# Nixie_Clock.net
KiCad netlist of a schematic drawn in EAGLE
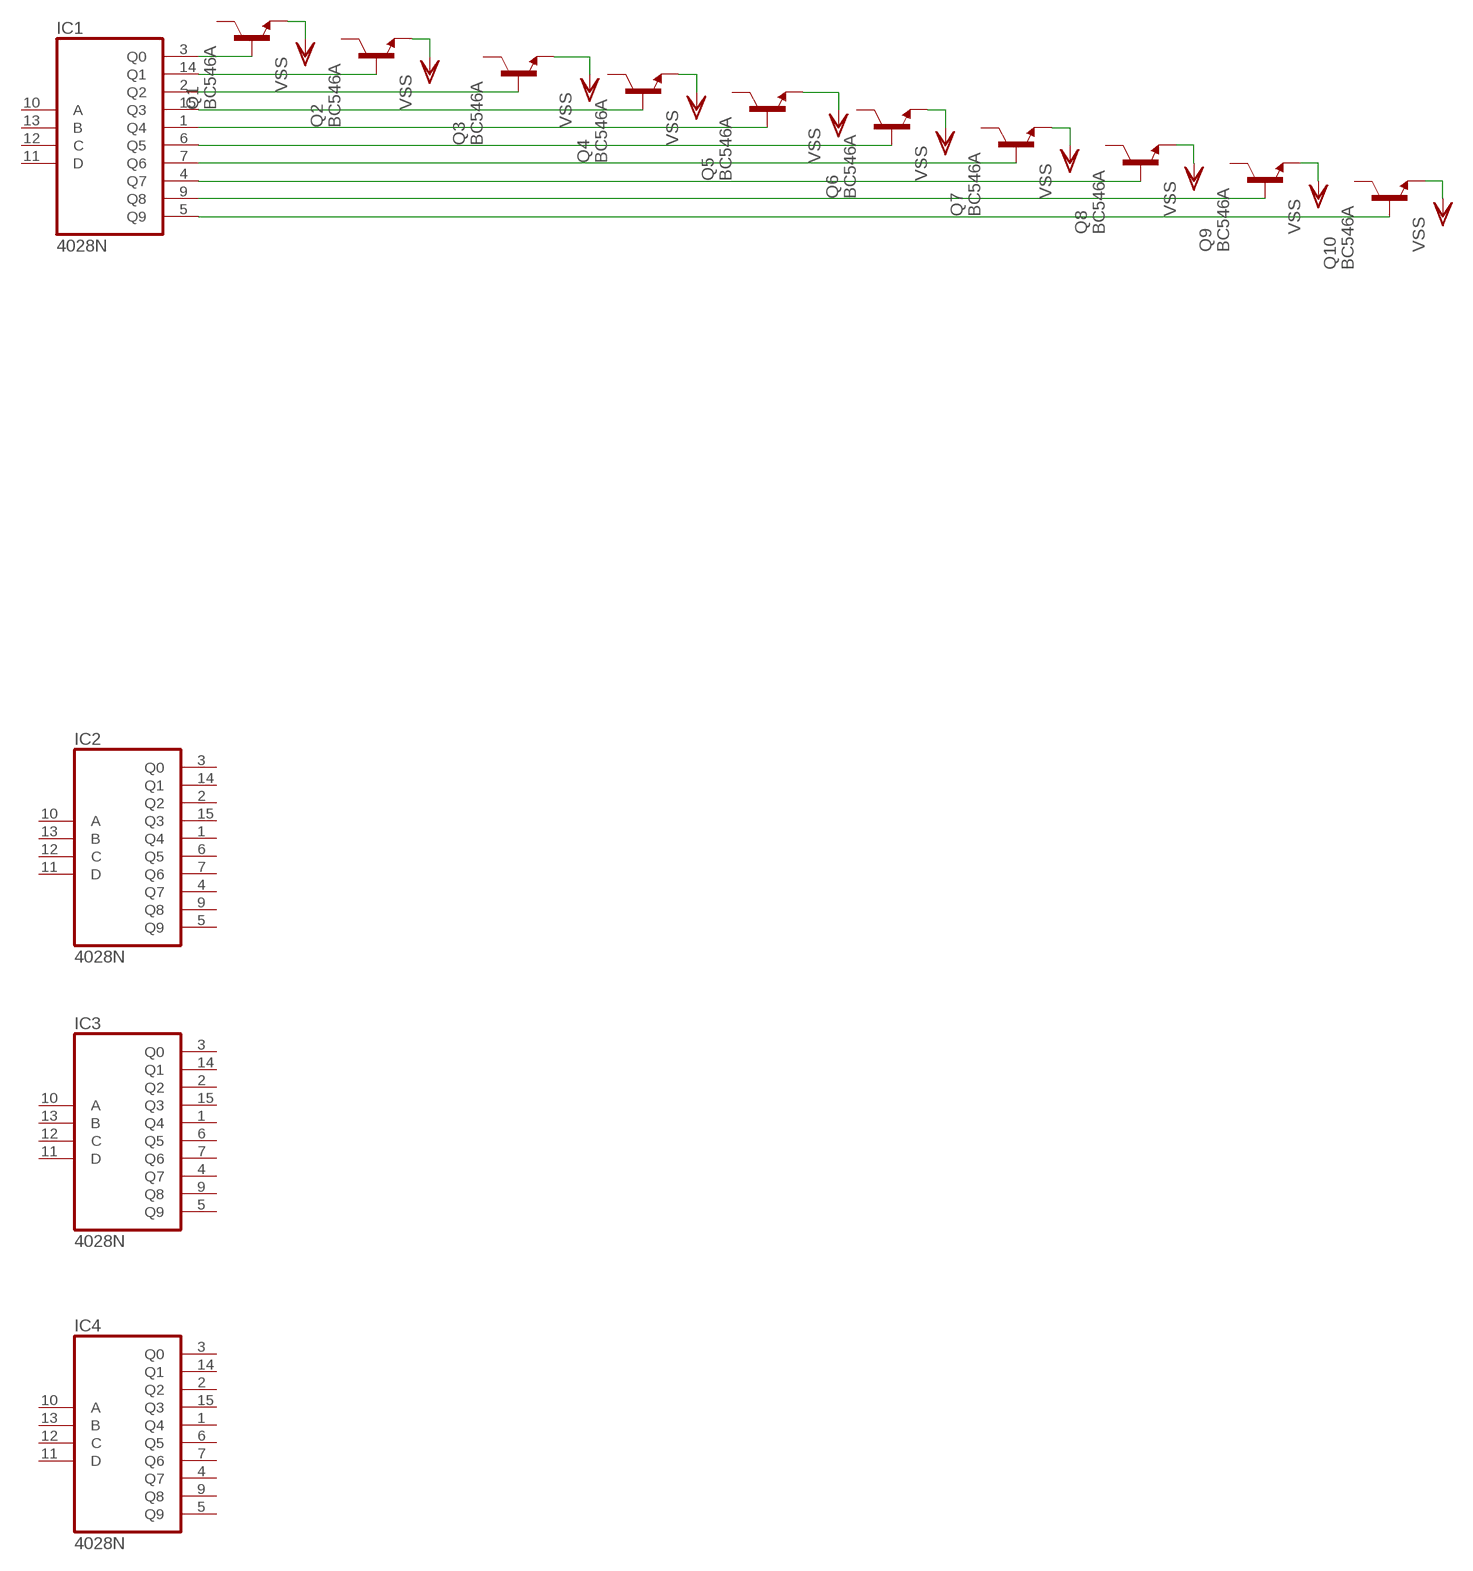
[diagram p0: schematic, sheet 1]

(export (version "E")
  (design (tool "Eeschema 10.0.6"))
  (components
    (comp (ref "IC1")
      (value "4028N")
      (footprint "eagle-import:DIL16")
      (libsource (lib "eagle-import") (part "4028N"))
    )
    (comp (ref "IC2")
      (value "4028N")
      (footprint "eagle-import:DIL16")
      (libsource (lib "eagle-import") (part "4028N"))
    )
    (comp (ref "IC3")
      (value "4028N")
      (footprint "eagle-import:DIL16")
      (libsource (lib "eagle-import") (part "4028N"))
    )
    (comp (ref "IC4")
      (value "4028N")
      (footprint "eagle-import:DIL16")
      (libsource (lib "eagle-import") (part "4028N"))
    )
    (comp (ref "Q1")
      (value "BC546A")
      (footprint "eagle-import:TO92-EBC")
      (libsource (lib "eagle-import") (part "BC546A"))
    )
    (comp (ref "Q2")
      (value "BC546A")
      (footprint "eagle-import:TO92-EBC")
      (libsource (lib "eagle-import") (part "BC546A"))
    )
    (comp (ref "Q3")
      (value "BC546A")
      (footprint "eagle-import:TO92-EBC")
      (libsource (lib "eagle-import") (part "BC546A"))
    )
    (comp (ref "Q4")
      (value "BC546A")
      (footprint "eagle-import:TO92-EBC")
      (libsource (lib "eagle-import") (part "BC546A"))
    )
    (comp (ref "Q5")
      (value "BC546A")
      (footprint "eagle-import:TO92-EBC")
      (libsource (lib "eagle-import") (part "BC546A"))
    )
    (comp (ref "Q6")
      (value "BC546A")
      (footprint "eagle-import:TO92-EBC")
      (libsource (lib "eagle-import") (part "BC546A"))
    )
    (comp (ref "Q7")
      (value "BC546A")
      (footprint "eagle-import:TO92-EBC")
      (libsource (lib "eagle-import") (part "BC546A"))
    )
    (comp (ref "Q8")
      (value "BC546A")
      (footprint "eagle-import:TO92-EBC")
      (libsource (lib "eagle-import") (part "BC546A"))
    )
    (comp (ref "Q9")
      (value "BC546A")
      (footprint "eagle-import:TO92-EBC")
      (libsource (lib "eagle-import") (part "BC546A"))
    )
    (comp (ref "Q10")
      (value "BC546A")
      (footprint "eagle-import:TO92-EBC")
      (libsource (lib "eagle-import") (part "BC546A"))
    )
  )
  (nets
    (net (code "1") (name "Net-(IC1A-Q0)") (class "Default")
      (node (ref "IC1") (pin "3") (pinfunction "Q0_3") (pintype "output"))
      (node (ref "Q1") (pin "B") (pinfunction "B_B") (pintype "passive"))
    )
    (net (code "2") (name "Net-(IC1A-Q1)") (class "Default")
      (node (ref "IC1") (pin "14") (pinfunction "Q1_14") (pintype "output"))
      (node (ref "Q2") (pin "B") (pinfunction "B_B") (pintype "passive"))
    )
    (net (code "3") (name "Net-(IC1A-Q2)") (class "Default")
      (node (ref "IC1") (pin "2") (pinfunction "Q2_2") (pintype "output"))
      (node (ref "Q3") (pin "B") (pinfunction "B_B") (pintype "passive"))
    )
    (net (code "4") (name "Net-(IC1A-Q3)") (class "Default")
      (node (ref "IC1") (pin "15") (pinfunction "Q3_15") (pintype "output"))
      (node (ref "Q4") (pin "B") (pinfunction "B_B") (pintype "passive"))
    )
    (net (code "5") (name "Net-(IC1A-Q4)") (class "Default")
      (node (ref "IC1") (pin "1") (pinfunction "Q4_1") (pintype "output"))
      (node (ref "Q5") (pin "B") (pinfunction "B_B") (pintype "passive"))
    )
    (net (code "6") (name "Net-(IC1A-Q5)") (class "Default")
      (node (ref "IC1") (pin "6") (pinfunction "Q5_6") (pintype "output"))
      (node (ref "Q6") (pin "B") (pinfunction "B_B") (pintype "passive"))
    )
    (net (code "7") (name "Net-(IC1A-Q6)") (class "Default")
      (node (ref "IC1") (pin "7") (pinfunction "Q6_7") (pintype "output"))
      (node (ref "Q7") (pin "B") (pinfunction "B_B") (pintype "passive"))
    )
    (net (code "8") (name "Net-(IC1A-Q7)") (class "Default")
      (node (ref "IC1") (pin "4") (pinfunction "Q7_4") (pintype "output"))
      (node (ref "Q8") (pin "B") (pinfunction "B_B") (pintype "passive"))
    )
    (net (code "9") (name "Net-(IC1A-Q8)") (class "Default")
      (node (ref "IC1") (pin "9") (pinfunction "Q8_9") (pintype "output"))
      (node (ref "Q9") (pin "B") (pinfunction "B_B") (pintype "passive"))
    )
    (net (code "10") (name "Net-(IC1A-Q9)") (class "Default")
      (node (ref "IC1") (pin "5") (pinfunction "Q9_5") (pintype "output"))
      (node (ref "Q10") (pin "B") (pinfunction "B_B") (pintype "passive"))
    )
    (net (code "11") (name "VSS") (class "Default")
      (node (ref "Q1") (pin "E") (pinfunction "E_E") (pintype "passive"))
      (node (ref "Q10") (pin "E") (pinfunction "E_E") (pintype "passive"))
      (node (ref "Q2") (pin "E") (pinfunction "E_E") (pintype "passive"))
      (node (ref "Q3") (pin "E") (pinfunction "E_E") (pintype "passive"))
      (node (ref "Q4") (pin "E") (pinfunction "E_E") (pintype "passive"))
      (node (ref "Q5") (pin "E") (pinfunction "E_E") (pintype "passive"))
      (node (ref "Q6") (pin "E") (pinfunction "E_E") (pintype "passive"))
      (node (ref "Q7") (pin "E") (pinfunction "E_E") (pintype "passive"))
      (node (ref "Q8") (pin "E") (pinfunction "E_E") (pintype "passive"))
      (node (ref "Q9") (pin "E") (pinfunction "E_E") (pintype "passive"))
    )
    (net (code "12") (name "unconnected-(IC1A-A-Pad10)") (class "Default")
      (node (ref "IC1") (pin "10") (pinfunction "A_10") (pintype "input"))
    )
    (net (code "13") (name "unconnected-(IC1A-B-Pad13)") (class "Default")
      (node (ref "IC1") (pin "13") (pinfunction "B_13") (pintype "input"))
    )
    (net (code "14") (name "unconnected-(IC1A-C-Pad12)") (class "Default")
      (node (ref "IC1") (pin "12") (pinfunction "C_12") (pintype "input"))
    )
    (net (code "15") (name "unconnected-(IC1A-D-Pad11)") (class "Default")
      (node (ref "IC1") (pin "11") (pinfunction "D_11") (pintype "input"))
    )
    (net (code "16") (name "unconnected-(IC2A-A-Pad10)") (class "Default")
      (node (ref "IC2") (pin "10") (pinfunction "A_10") (pintype "input"))
    )
    (net (code "17") (name "unconnected-(IC2A-B-Pad13)") (class "Default")
      (node (ref "IC2") (pin "13") (pinfunction "B_13") (pintype "input"))
    )
    (net (code "18") (name "unconnected-(IC2A-C-Pad12)") (class "Default")
      (node (ref "IC2") (pin "12") (pinfunction "C_12") (pintype "input"))
    )
    (net (code "19") (name "unconnected-(IC2A-D-Pad11)") (class "Default")
      (node (ref "IC2") (pin "11") (pinfunction "D_11") (pintype "input"))
    )
    (net (code "20") (name "unconnected-(IC2A-Q0-Pad3)") (class "Default")
      (node (ref "IC2") (pin "3") (pinfunction "Q0_3") (pintype "output"))
    )
    (net (code "21") (name "unconnected-(IC2A-Q1-Pad14)") (class "Default")
      (node (ref "IC2") (pin "14") (pinfunction "Q1_14") (pintype "output"))
    )
    (net (code "22") (name "unconnected-(IC2A-Q2-Pad2)") (class "Default")
      (node (ref "IC2") (pin "2") (pinfunction "Q2_2") (pintype "output"))
    )
    (net (code "23") (name "unconnected-(IC2A-Q3-Pad15)") (class "Default")
      (node (ref "IC2") (pin "15") (pinfunction "Q3_15") (pintype "output"))
    )
    (net (code "24") (name "unconnected-(IC2A-Q4-Pad1)") (class "Default")
      (node (ref "IC2") (pin "1") (pinfunction "Q4_1") (pintype "output"))
    )
    (net (code "25") (name "unconnected-(IC2A-Q5-Pad6)") (class "Default")
      (node (ref "IC2") (pin "6") (pinfunction "Q5_6") (pintype "output"))
    )
    (net (code "26") (name "unconnected-(IC2A-Q6-Pad7)") (class "Default")
      (node (ref "IC2") (pin "7") (pinfunction "Q6_7") (pintype "output"))
    )
    (net (code "27") (name "unconnected-(IC2A-Q7-Pad4)") (class "Default")
      (node (ref "IC2") (pin "4") (pinfunction "Q7_4") (pintype "output"))
    )
    (net (code "28") (name "unconnected-(IC2A-Q8-Pad9)") (class "Default")
      (node (ref "IC2") (pin "9") (pinfunction "Q8_9") (pintype "output"))
    )
    (net (code "29") (name "unconnected-(IC2A-Q9-Pad5)") (class "Default")
      (node (ref "IC2") (pin "5") (pinfunction "Q9_5") (pintype "output"))
    )
    (net (code "30") (name "unconnected-(IC3A-A-Pad10)") (class "Default")
      (node (ref "IC3") (pin "10") (pinfunction "A_10") (pintype "input"))
    )
    (net (code "31") (name "unconnected-(IC3A-B-Pad13)") (class "Default")
      (node (ref "IC3") (pin "13") (pinfunction "B_13") (pintype "input"))
    )
    (net (code "32") (name "unconnected-(IC3A-C-Pad12)") (class "Default")
      (node (ref "IC3") (pin "12") (pinfunction "C_12") (pintype "input"))
    )
    (net (code "33") (name "unconnected-(IC3A-D-Pad11)") (class "Default")
      (node (ref "IC3") (pin "11") (pinfunction "D_11") (pintype "input"))
    )
    (net (code "34") (name "unconnected-(IC3A-Q0-Pad3)") (class "Default")
      (node (ref "IC3") (pin "3") (pinfunction "Q0_3") (pintype "output"))
    )
    (net (code "35") (name "unconnected-(IC3A-Q1-Pad14)") (class "Default")
      (node (ref "IC3") (pin "14") (pinfunction "Q1_14") (pintype "output"))
    )
    (net (code "36") (name "unconnected-(IC3A-Q2-Pad2)") (class "Default")
      (node (ref "IC3") (pin "2") (pinfunction "Q2_2") (pintype "output"))
    )
    (net (code "37") (name "unconnected-(IC3A-Q3-Pad15)") (class "Default")
      (node (ref "IC3") (pin "15") (pinfunction "Q3_15") (pintype "output"))
    )
    (net (code "38") (name "unconnected-(IC3A-Q4-Pad1)") (class "Default")
      (node (ref "IC3") (pin "1") (pinfunction "Q4_1") (pintype "output"))
    )
    (net (code "39") (name "unconnected-(IC3A-Q5-Pad6)") (class "Default")
      (node (ref "IC3") (pin "6") (pinfunction "Q5_6") (pintype "output"))
    )
    (net (code "40") (name "unconnected-(IC3A-Q6-Pad7)") (class "Default")
      (node (ref "IC3") (pin "7") (pinfunction "Q6_7") (pintype "output"))
    )
    (net (code "41") (name "unconnected-(IC3A-Q7-Pad4)") (class "Default")
      (node (ref "IC3") (pin "4") (pinfunction "Q7_4") (pintype "output"))
    )
    (net (code "42") (name "unconnected-(IC3A-Q8-Pad9)") (class "Default")
      (node (ref "IC3") (pin "9") (pinfunction "Q8_9") (pintype "output"))
    )
    (net (code "43") (name "unconnected-(IC3A-Q9-Pad5)") (class "Default")
      (node (ref "IC3") (pin "5") (pinfunction "Q9_5") (pintype "output"))
    )
    (net (code "44") (name "unconnected-(IC4A-A-Pad10)") (class "Default")
      (node (ref "IC4") (pin "10") (pinfunction "A_10") (pintype "input"))
    )
    (net (code "45") (name "unconnected-(IC4A-B-Pad13)") (class "Default")
      (node (ref "IC4") (pin "13") (pinfunction "B_13") (pintype "input"))
    )
    (net (code "46") (name "unconnected-(IC4A-C-Pad12)") (class "Default")
      (node (ref "IC4") (pin "12") (pinfunction "C_12") (pintype "input"))
    )
    (net (code "47") (name "unconnected-(IC4A-D-Pad11)") (class "Default")
      (node (ref "IC4") (pin "11") (pinfunction "D_11") (pintype "input"))
    )
    (net (code "48") (name "unconnected-(IC4A-Q0-Pad3)") (class "Default")
      (node (ref "IC4") (pin "3") (pinfunction "Q0_3") (pintype "output"))
    )
    (net (code "49") (name "unconnected-(IC4A-Q1-Pad14)") (class "Default")
      (node (ref "IC4") (pin "14") (pinfunction "Q1_14") (pintype "output"))
    )
    (net (code "50") (name "unconnected-(IC4A-Q2-Pad2)") (class "Default")
      (node (ref "IC4") (pin "2") (pinfunction "Q2_2") (pintype "output"))
    )
    (net (code "51") (name "unconnected-(IC4A-Q3-Pad15)") (class "Default")
      (node (ref "IC4") (pin "15") (pinfunction "Q3_15") (pintype "output"))
    )
    (net (code "52") (name "unconnected-(IC4A-Q4-Pad1)") (class "Default")
      (node (ref "IC4") (pin "1") (pinfunction "Q4_1") (pintype "output"))
    )
    (net (code "53") (name "unconnected-(IC4A-Q5-Pad6)") (class "Default")
      (node (ref "IC4") (pin "6") (pinfunction "Q5_6") (pintype "output"))
    )
    (net (code "54") (name "unconnected-(IC4A-Q6-Pad7)") (class "Default")
      (node (ref "IC4") (pin "7") (pinfunction "Q6_7") (pintype "output"))
    )
    (net (code "55") (name "unconnected-(IC4A-Q7-Pad4)") (class "Default")
      (node (ref "IC4") (pin "4") (pinfunction "Q7_4") (pintype "output"))
    )
    (net (code "56") (name "unconnected-(IC4A-Q8-Pad9)") (class "Default")
      (node (ref "IC4") (pin "9") (pinfunction "Q8_9") (pintype "output"))
    )
    (net (code "57") (name "unconnected-(IC4A-Q9-Pad5)") (class "Default")
      (node (ref "IC4") (pin "5") (pinfunction "Q9_5") (pintype "output"))
    )
    (net (code "58") (name "unconnected-(Q1-PadC)") (class "Default")
      (node (ref "Q1") (pin "C") (pinfunction "C_C") (pintype "passive"))
    )
    (net (code "59") (name "unconnected-(Q2-PadC)") (class "Default")
      (node (ref "Q2") (pin "C") (pinfunction "C_C") (pintype "passive"))
    )
    (net (code "60") (name "unconnected-(Q3-PadC)") (class "Default")
      (node (ref "Q3") (pin "C") (pinfunction "C_C") (pintype "passive"))
    )
    (net (code "61") (name "unconnected-(Q4-PadC)") (class "Default")
      (node (ref "Q4") (pin "C") (pinfunction "C_C") (pintype "passive"))
    )
    (net (code "62") (name "unconnected-(Q5-PadC)") (class "Default")
      (node (ref "Q5") (pin "C") (pinfunction "C_C") (pintype "passive"))
    )
    (net (code "63") (name "unconnected-(Q6-PadC)") (class "Default")
      (node (ref "Q6") (pin "C") (pinfunction "C_C") (pintype "passive"))
    )
    (net (code "64") (name "unconnected-(Q7-PadC)") (class "Default")
      (node (ref "Q7") (pin "C") (pinfunction "C_C") (pintype "passive"))
    )
    (net (code "65") (name "unconnected-(Q8-PadC)") (class "Default")
      (node (ref "Q8") (pin "C") (pinfunction "C_C") (pintype "passive"))
    )
    (net (code "66") (name "unconnected-(Q9-PadC)") (class "Default")
      (node (ref "Q9") (pin "C") (pinfunction "C_C") (pintype "passive"))
    )
    (net (code "67") (name "unconnected-(Q10-PadC)") (class "Default")
      (node (ref "Q10") (pin "C") (pinfunction "C_C") (pintype "passive"))
    )
  )
)
